# Charger.net
KiCad netlist of a schematic drawn in Altium Designer
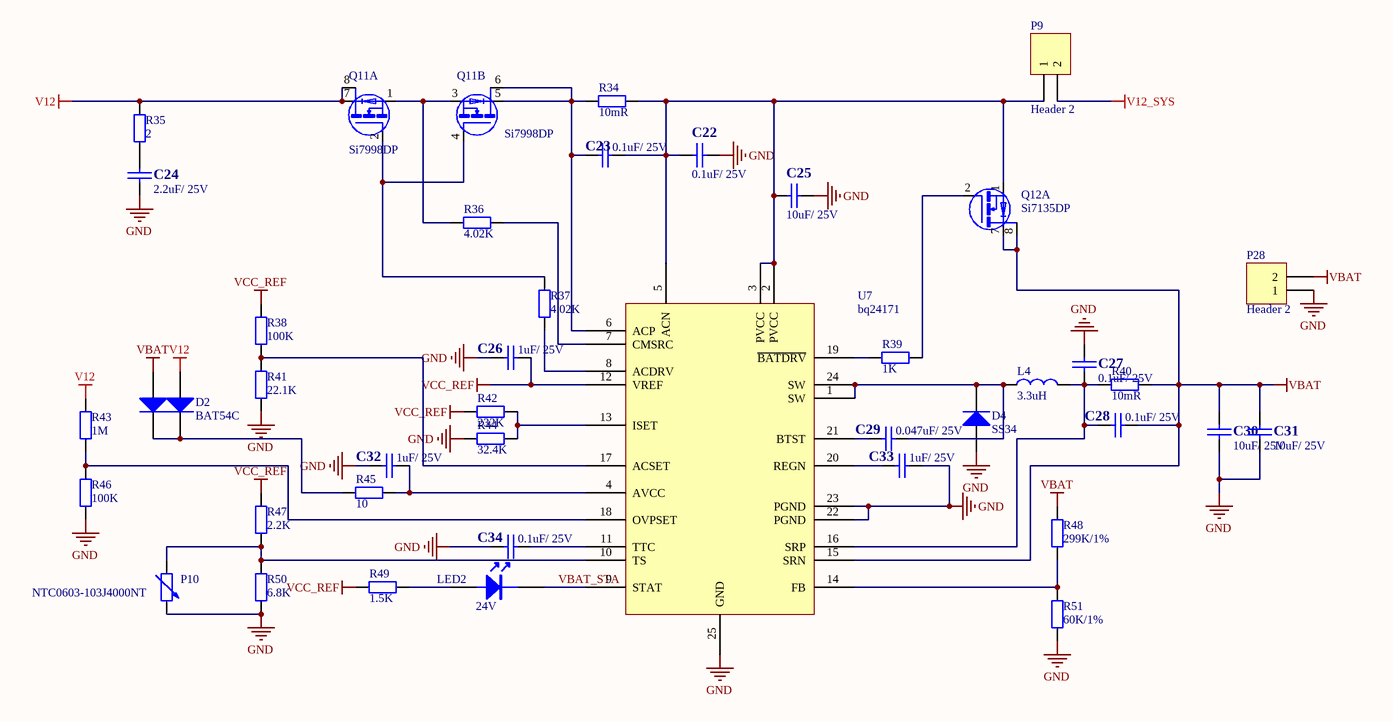
[diagram p0: Charger.SchDoc]

(export (version "E")
  (design (tool "Eeschema 10.0.6"))
  (components
    (comp (ref "C22")
      (value "0.1uF/ 25V")
      (footprint "0603C")
      (description "Capacitor")
      (libsource (lib "*") (part "CAP"))
    )
    (comp (ref "C23")
      (value "0.1uF/ 25V")
      (footprint "0603C")
      (description "Capacitor")
      (libsource (lib "*") (part "CAP"))
    )
    (comp (ref "C24")
      (value "2.2uF/ 25V")
      (footprint "0603C")
      (description "Capacitor")
      (libsource (lib "*") (part "CAP"))
    )
    (comp (ref "C25")
      (value "10uF/ 25V")
      (footprint "0603C")
      (description "Capacitor")
      (libsource (lib "*") (part "CAP"))
    )
    (comp (ref "C26")
      (value "1uF/ 25V")
      (footprint "0603C")
      (description "Capacitor")
      (libsource (lib "*") (part "CAP"))
    )
    (comp (ref "C27")
      (value "0.1uF/ 25V")
      (footprint "0603C")
      (description "Capacitor")
      (libsource (lib "*") (part "CAP"))
    )
    (comp (ref "C28")
      (value "0.1uF/ 25V")
      (footprint "0603C")
      (description "Capacitor")
      (libsource (lib "*") (part "CAP"))
    )
    (comp (ref "C29")
      (value "0.047uF/ 25V")
      (footprint "0603C")
      (description "Capacitor")
      (libsource (lib "*") (part "CAP"))
    )
    (comp (ref "C30")
      (value "10uF/ 25V")
      (footprint "0603C")
      (description "Capacitor")
      (libsource (lib "*") (part "CAP"))
    )
    (comp (ref "C31")
      (value "10uF/ 25V")
      (footprint "0603C")
      (description "Capacitor")
      (libsource (lib "*") (part "CAP"))
    )
    (comp (ref "C32")
      (value "1uF/ 25V")
      (footprint "0603C")
      (description "Capacitor")
      (libsource (lib "*") (part "CAP"))
    )
    (comp (ref "C33")
      (value "1uF/ 25V")
      (footprint "0603C")
      (description "Capacitor")
      (libsource (lib "*") (part "CAP"))
    )
    (comp (ref "C34")
      (value "0.1uF/ 25V")
      (footprint "0603C")
      (description "Capacitor")
      (libsource (lib "*") (part "CAP"))
    )
    (comp (ref "D2") (value "BAT54C") (footprint "SOT23-3") (libsource (lib "stm32") (part "BAT54C")))
    (comp (ref "D4") (value "SS34") (footprint "SMA") (libsource (lib "Sch_library") (part "DIODE")))
    (comp (ref "L4") (value "3.3uH") (footprint "CDRH-127") (libsource (lib "Sch_library") (part "IND")))
    (comp (ref "LED2") (value "24V") (footprint "0603LED") (libsource (lib "*") (part "LED")))
    (comp (ref "P9")
      (value "Header 2")
      (footprint "HDR1X2")
      (description "Header, 2-Pin")
      (fields (field (name "PUBLISHER") "Altium Limited"))
      (libsource (lib "Miscellaneous Connectors") (part "Header 2"))
    )
    (comp (ref "P10")
      (value "NTC0603-103J4000NT")
      (footprint "SMD-0603")
      (description "卧贴")
      (libsource (lib "ABB") (part "RES3"))
    )
    (comp (ref "P28")
      (value "Header 2")
      (footprint "HDR1X2")
      (description "Header, 2-Pin")
      (fields (field (name "PUBLISHER") "Altium Limited"))
      (libsource (lib "") (part "Header 2_1"))
    )
    (comp (ref "Q11") (value "Si7998DP") (footprint "PowerPAK SO-8") (libsource (lib "") (part "SI7940DP_2")))
    (comp (ref "Q12")
      (value "Si7135DP")
      (footprint "PowerPAK SO-8")
      (libsource (lib "Y0801_V14") (part "SI7940DP"))
    )
    (comp (ref "R34")
      (value "10mR")
      (footprint "2512R")
      (description "贴片电阻 5%")
      (libsource (lib "XiaoyI") (part "RES2"))
    )
    (comp (ref "R35")
      (value "2")
      (footprint "SMD-0603")
      (description "贴片电阻 5%")
      (libsource (lib "") (part "RES2_1"))
    )
    (comp (ref "R36")
      (value "4.02K")
      (footprint "SMD-0603")
      (description "贴片电阻 5%")
      (libsource (lib "XiaoyI") (part "RES2"))
    )
    (comp (ref "R37")
      (value "4.02K")
      (footprint "SMD-0603")
      (description "贴片电阻 5%")
      (libsource (lib "") (part "RES2_1"))
    )
    (comp (ref "R38")
      (value "100K")
      (footprint "SMD-0603")
      (description "贴片电阻 5%")
      (libsource (lib "") (part "RES2_1"))
    )
    (comp (ref "R39")
      (value "1K")
      (footprint "2512R")
      (description "贴片电阻 5%")
      (libsource (lib "XiaoyI") (part "RES2"))
    )
    (comp (ref "R40")
      (value "10mR")
      (footprint "2512R")
      (description "贴片电阻 5%")
      (libsource (lib "XiaoyI") (part "RES2"))
    )
    (comp (ref "R41")
      (value "22.1K")
      (footprint "SMD-0603")
      (description "贴片电阻 5%")
      (libsource (lib "") (part "RES2_1"))
    )
    (comp (ref "R42")
      (value "232K")
      (footprint "SMD-0603")
      (description "贴片电阻 5%")
      (libsource (lib "XiaoyI") (part "RES2"))
    )
    (comp (ref "R43")
      (value "1M")
      (footprint "SMD-0603")
      (description "贴片电阻 5%")
      (libsource (lib "") (part "RES2_1"))
    )
    (comp (ref "R44")
      (value "32.4K")
      (footprint "SMD-0603")
      (description "贴片电阻 5%")
      (libsource (lib "XiaoyI") (part "RES2"))
    )
    (comp (ref "R45")
      (value "10")
      (footprint "SMD-0603")
      (description "贴片电阻 5%")
      (libsource (lib "XiaoyI") (part "RES2"))
    )
    (comp (ref "R46")
      (value "100K")
      (footprint "SMD-0603")
      (description "贴片电阻 5%")
      (libsource (lib "") (part "RES2_1"))
    )
    (comp (ref "R47")
      (value "2.2K")
      (footprint "SMD-0603")
      (description "贴片电阻 5%")
      (libsource (lib "") (part "RES2_1"))
    )
    (comp (ref "R48")
      (value "299K/1%")
      (footprint "SMD-0603")
      (description "贴片电阻 5%")
      (libsource (lib "") (part "RES2_2"))
    )
    (comp (ref "R49")
      (value "1.5K")
      (footprint "SMD-0603")
      (description "贴片电阻 5%")
      (libsource (lib "XiaoyI") (part "RES2"))
    )
    (comp (ref "R50")
      (value "6.8K")
      (footprint "SMD-0603")
      (description "贴片电阻 5%")
      (libsource (lib "") (part "RES2_1"))
    )
    (comp (ref "R51")
      (value "60K/1%")
      (footprint "SMD-0603")
      (description "贴片电阻 5%")
      (libsource (lib "") (part "RES2_2"))
    )
    (comp (ref "U7") (value "bq24171") (footprint "bq24171") (libsource (lib "stm32") (part "bq24171")))
  )
  (nets
    (net (code "1") (name "/VBAT_STA") (class "Default")
      (node (ref "LED2") (pin "2") (pinfunction "2_2") (pintype "passive"))
      (node (ref "U7") (pin "9") (pinfunction "STAT_9") (pintype "passive"))
    )
    (net (code "2") (name "GND") (class "Default")
      (node (ref "C22") (pin "2") (pinfunction "2_2") (pintype "passive"))
      (node (ref "C24") (pin "2") (pinfunction "2_2") (pintype "passive"))
      (node (ref "C25") (pin "2") (pinfunction "2_2") (pintype "passive"))
      (node (ref "C26") (pin "2") (pinfunction "2_2") (pintype "passive"))
      (node (ref "C27") (pin "1") (pinfunction "1_1") (pintype "passive"))
      (node (ref "C30") (pin "2") (pinfunction "2_2") (pintype "passive"))
      (node (ref "C31") (pin "2") (pinfunction "2_2") (pintype "passive"))
      (node (ref "C32") (pin "2") (pinfunction "2_2") (pintype "passive"))
      (node (ref "C33") (pin "1") (pinfunction "1_1") (pintype "passive"))
      (node (ref "C34") (pin "2") (pinfunction "2_2") (pintype "passive"))
      (node (ref "D4") (pin "1") (pinfunction "A_1") (pintype "passive"))
      (node (ref "P10") (pin "2") (pinfunction "2_2") (pintype "passive"))
      (node (ref "P28") (pin "1") (pinfunction "1_1") (pintype "passive"))
      (node (ref "R41") (pin "1") (pinfunction "1_1") (pintype "passive"))
      (node (ref "R44") (pin "1") (pinfunction "1_1") (pintype "passive"))
      (node (ref "R46") (pin "1") (pinfunction "1_1") (pintype "passive"))
      (node (ref "R50") (pin "1") (pinfunction "1_1") (pintype "passive"))
      (node (ref "R51") (pin "2") (pinfunction "2_2") (pintype "passive"))
      (node (ref "U7") (pin "22") (pinfunction "PGND_22") (pintype "passive"))
      (node (ref "U7") (pin "23") (pinfunction "PGND_23") (pintype "passive"))
      (node (ref "U7") (pin "25") (pinfunction "GND_25") (pintype "passive"))
    )
    (net (code "3") (name "Net-(C24-Pad1)") (class "Default")
      (node (ref "C24") (pin "1") (pinfunction "1_1") (pintype "passive"))
      (node (ref "R35") (pin "1") (pinfunction "1_1") (pintype "passive"))
    )
    (net (code "4") (name "Net-(D2-K)") (class "Default")
      (node (ref "D2") (pin "3") (pinfunction "K_3") (pintype "passive"))
      (node (ref "R45") (pin "1") (pinfunction "1_1") (pintype "passive"))
    )
    (net (code "5") (name "Net-(D4-K)") (class "Default")
      (node (ref "C29") (pin "1") (pinfunction "1_1") (pintype "passive"))
      (node (ref "D4") (pin "2") (pinfunction "K_2") (pintype "passive"))
      (node (ref "L4") (pin "1") (pinfunction "1_1") (pintype "passive"))
      (node (ref "U7") (pin "1") (pinfunction "SW_1") (pintype "passive"))
      (node (ref "U7") (pin "24") (pinfunction "SW_24") (pintype "passive"))
    )
    (net (code "6") (name "Net-(LED2-Pad1)") (class "Default")
      (node (ref "LED2") (pin "1") (pinfunction "1_1") (pintype "passive"))
      (node (ref "R49") (pin "2") (pinfunction "2_2") (pintype "passive"))
    )
    (net (code "7") (name "Net-(Q11A-G1)") (class "Default")
      (node (ref "Q11") (pin "2") (pinfunction "G1_2") (pintype "passive"))
      (node (ref "Q11") (pin "4") (pinfunction "G2_4") (pintype "passive"))
      (node (ref "R37") (pin "2") (pinfunction "2_2") (pintype "passive"))
    )
    (net (code "8") (name "Net-(Q11A-S1)") (class "Default")
      (node (ref "Q11") (pin "1") (pinfunction "S1_1") (pintype "passive"))
      (node (ref "Q11") (pin "3") (pinfunction "S2_3") (pintype "passive"))
      (node (ref "R36") (pin "1") (pinfunction "1_1") (pintype "passive"))
    )
    (net (code "9") (name "Net-(Q12A-G1)") (class "Default")
      (node (ref "Q12") (pin "2") (pinfunction "G1_2") (pintype "passive"))
      (node (ref "R39") (pin "2") (pinfunction "2_2") (pintype "passive"))
    )
    (net (code "10") (name "Net-(Q12A-S1)") (class "Default")
      (node (ref "C22") (pin "1") (pinfunction "1_1") (pintype "passive"))
      (node (ref "C23") (pin "2") (pinfunction "2_2") (pintype "passive"))
      (node (ref "C25") (pin "1") (pinfunction "1_1") (pintype "passive"))
      (node (ref "P9") (pin "1") (pinfunction "1_1") (pintype "passive"))
      (node (ref "Q12") (pin "1") (pinfunction "S1_1") (pintype "passive"))
      (node (ref "R34") (pin "2") (pinfunction "2_2") (pintype "passive"))
      (node (ref "U7") (pin "2") (pinfunction "PVCC_2") (pintype "passive"))
      (node (ref "U7") (pin "3") (pinfunction "PVCC_3") (pintype "passive"))
      (node (ref "U7") (pin "5") (pinfunction "ACN_5") (pintype "passive"))
    )
    (net (code "11") (name "Net-(U7-ACDRV)") (class "Default")
      (node (ref "R37") (pin "1") (pinfunction "1_1") (pintype "passive"))
      (node (ref "U7") (pin "8") (pinfunction "ACDRV_8") (pintype "passive"))
    )
    (net (code "12") (name "Net-(U7-ACP)") (class "Default")
      (node (ref "C23") (pin "1") (pinfunction "1_1") (pintype "passive"))
      (node (ref "Q11") (pin "5") (pinfunction "D2_5") (pintype "passive"))
      (node (ref "Q11") (pin "6") (pinfunction "D2_6") (pintype "passive"))
      (node (ref "R34") (pin "1") (pinfunction "1_1") (pintype "passive"))
      (node (ref "U7") (pin "6") (pinfunction "ACP_6") (pintype "passive"))
    )
    (net (code "13") (name "Net-(U7-ACSET)") (class "Default")
      (node (ref "R38") (pin "1") (pinfunction "1_1") (pintype "passive"))
      (node (ref "R41") (pin "2") (pinfunction "2_2") (pintype "passive"))
      (node (ref "U7") (pin "17") (pinfunction "ACSET_17") (pintype "passive"))
    )
    (net (code "14") (name "Net-(U7-AVCC)") (class "Default")
      (node (ref "C32") (pin "1") (pinfunction "1_1") (pintype "passive"))
      (node (ref "R45") (pin "2") (pinfunction "2_2") (pintype "passive"))
      (node (ref "U7") (pin "4") (pinfunction "AVCC_4") (pintype "passive"))
    )
    (net (code "15") (name "Net-(U7-BTST)") (class "Default")
      (node (ref "C29") (pin "2") (pinfunction "2_2") (pintype "passive"))
      (node (ref "U7") (pin "21") (pinfunction "BTST_21") (pintype "passive"))
    )
    (net (code "16") (name "Net-(U7-CMSRC)") (class "Default")
      (node (ref "R36") (pin "2") (pinfunction "2_2") (pintype "passive"))
      (node (ref "U7") (pin "7") (pinfunction "CMSRC_7") (pintype "passive"))
    )
    (net (code "17") (name "Net-(U7-FB)") (class "Default")
      (node (ref "R48") (pin "2") (pinfunction "2_2") (pintype "passive"))
      (node (ref "R51") (pin "1") (pinfunction "1_1") (pintype "passive"))
      (node (ref "U7") (pin "14") (pinfunction "FB_14") (pintype "passive"))
    )
    (net (code "18") (name "Net-(U7-ISET)") (class "Default")
      (node (ref "R42") (pin "2") (pinfunction "2_2") (pintype "passive"))
      (node (ref "R44") (pin "2") (pinfunction "2_2") (pintype "passive"))
      (node (ref "U7") (pin "13") (pinfunction "ISET_13") (pintype "passive"))
    )
    (net (code "19") (name "Net-(U7-OVPSET)") (class "Default")
      (node (ref "R43") (pin "1") (pinfunction "1_1") (pintype "passive"))
      (node (ref "R46") (pin "2") (pinfunction "2_2") (pintype "passive"))
      (node (ref "U7") (pin "18") (pinfunction "OVPSET_18") (pintype "passive"))
    )
    (net (code "20") (name "Net-(U7-REGN)") (class "Default")
      (node (ref "C33") (pin "2") (pinfunction "2_2") (pintype "passive"))
      (node (ref "U7") (pin "20") (pinfunction "REGN_20") (pintype "passive"))
    )
    (net (code "21") (name "Net-(U7-SRP)") (class "Default")
      (node (ref "C27") (pin "2") (pinfunction "2_2") (pintype "passive"))
      (node (ref "C28") (pin "2") (pinfunction "2_2") (pintype "passive"))
      (node (ref "L4") (pin "2") (pinfunction "2_2") (pintype "passive"))
      (node (ref "R40") (pin "1") (pinfunction "1_1") (pintype "passive"))
      (node (ref "U7") (pin "16") (pinfunction "SRP_16") (pintype "passive"))
    )
    (net (code "22") (name "Net-(U7-TS)") (class "Default")
      (node (ref "P10") (pin "1") (pinfunction "1_1") (pintype "passive"))
      (node (ref "R47") (pin "1") (pinfunction "1_1") (pintype "passive"))
      (node (ref "R50") (pin "2") (pinfunction "2_2") (pintype "passive"))
      (node (ref "U7") (pin "10") (pinfunction "TS_10") (pintype "passive"))
    )
    (net (code "23") (name "Net-(U7-TTC)") (class "Default")
      (node (ref "C34") (pin "1") (pinfunction "1_1") (pintype "passive"))
      (node (ref "U7") (pin "11") (pinfunction "TTC_11") (pintype "passive"))
    )
    (net (code "24") (name "Net-(U7-~{BATDRV})") (class "Default")
      (node (ref "R39") (pin "1") (pinfunction "1_1") (pintype "passive"))
      (node (ref "U7") (pin "19") (pinfunction "~{BATDRV}_19") (pintype "passive"))
    )
    (net (code "25") (name "V12") (class "Default")
      (node (ref "D2") (pin "1") (pinfunction "A_1") (pintype "passive"))
      (node (ref "Q11") (pin "7") (pinfunction "D1_7") (pintype "passive"))
      (node (ref "Q11") (pin "8") (pinfunction "D1_8") (pintype "passive"))
      (node (ref "R35") (pin "2") (pinfunction "2_2") (pintype "passive"))
      (node (ref "R43") (pin "2") (pinfunction "2_2") (pintype "passive"))
    )
    (net (code "26") (name "V12_SYS") (class "Default")
      (node (ref "P9") (pin "2") (pinfunction "2_2") (pintype "passive"))
    )
    (net (code "27") (name "VBAT") (class "Default")
      (node (ref "C28") (pin "1") (pinfunction "1_1") (pintype "passive"))
      (node (ref "C30") (pin "1") (pinfunction "1_1") (pintype "passive"))
      (node (ref "C31") (pin "1") (pinfunction "1_1") (pintype "passive"))
      (node (ref "D2") (pin "2") (pinfunction "A_2") (pintype "passive"))
      (node (ref "P28") (pin "2") (pinfunction "2_2") (pintype "passive"))
      (node (ref "Q12") (pin "7") (pinfunction "D1_7") (pintype "passive"))
      (node (ref "Q12") (pin "8") (pinfunction "D1_8") (pintype "passive"))
      (node (ref "R40") (pin "2") (pinfunction "2_2") (pintype "passive"))
      (node (ref "R48") (pin "1") (pinfunction "1_1") (pintype "passive"))
      (node (ref "U7") (pin "15") (pinfunction "SRN_15") (pintype "passive"))
    )
    (net (code "28") (name "VCC_REF") (class "Default")
      (node (ref "C26") (pin "1") (pinfunction "1_1") (pintype "passive"))
      (node (ref "R38") (pin "2") (pinfunction "2_2") (pintype "passive"))
      (node (ref "R42") (pin "1") (pinfunction "1_1") (pintype "passive"))
      (node (ref "R47") (pin "2") (pinfunction "2_2") (pintype "passive"))
      (node (ref "R49") (pin "1") (pinfunction "1_1") (pintype "passive"))
      (node (ref "U7") (pin "12") (pinfunction "VREF_12") (pintype "passive"))
    )
  )
)
